# LAB_20200609_0_LightSensorWithNPN.net
KiCad netlist of a schematic drawn in EAGLE
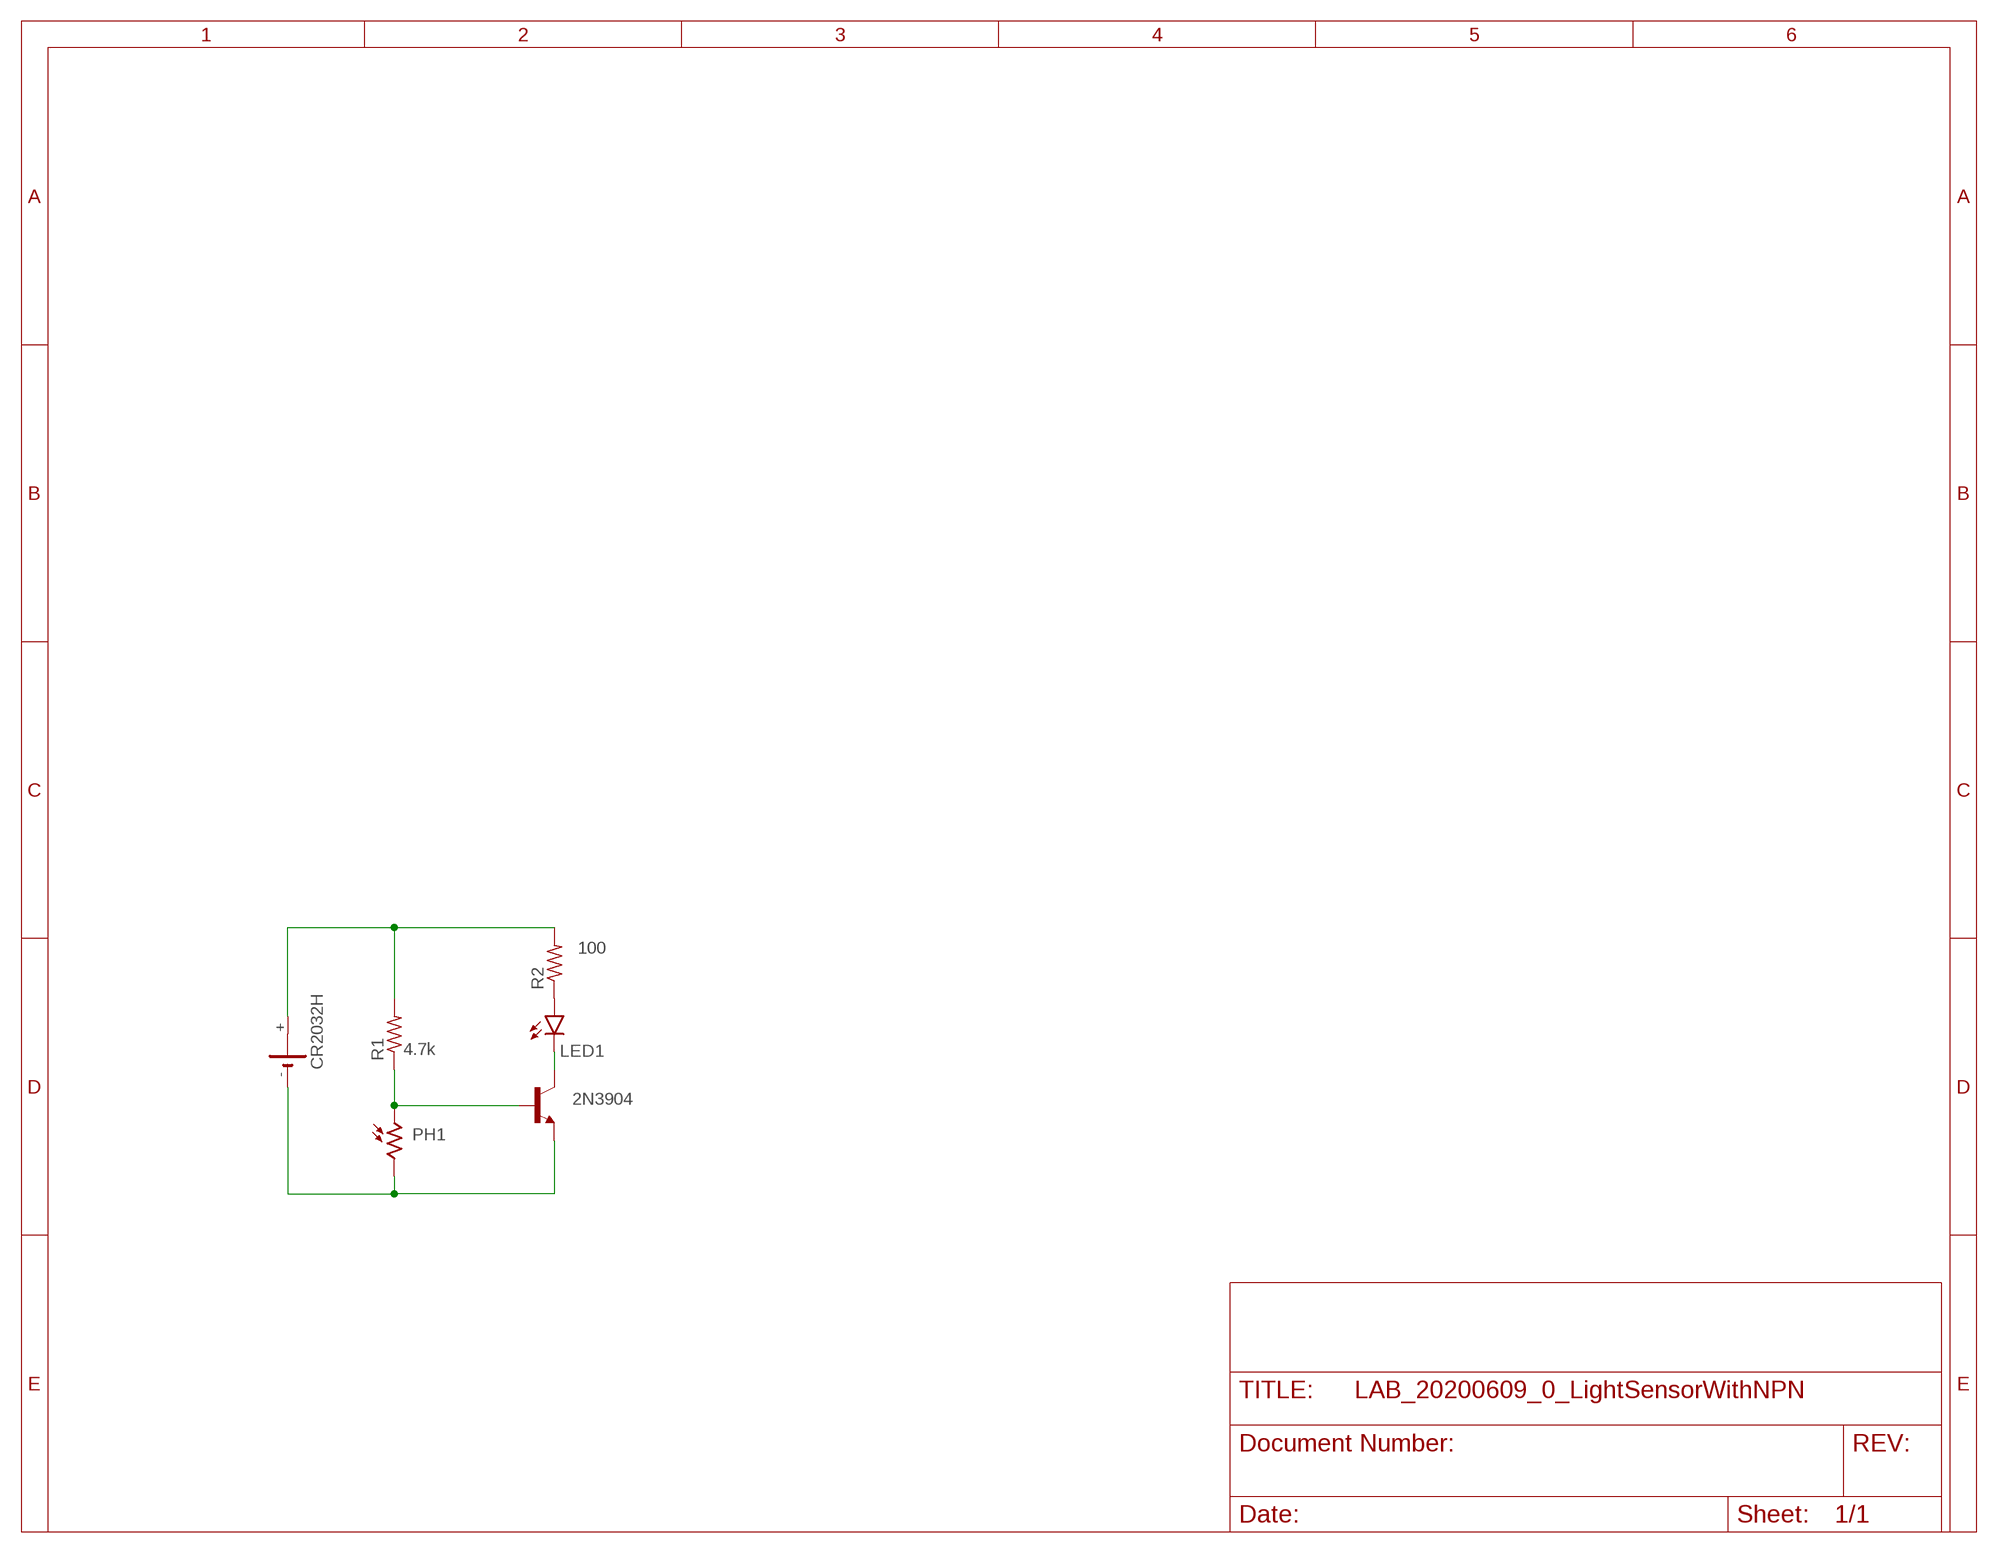
[diagram p0: schematic, sheet 1]

(export (version "E")
  (design (tool "Eeschema 10.0.6"))
  (components
    (comp (ref "G1")
      (value "CR2032H")
      (footprint "eagle-import:CR2032H")
      (libsource (lib "eagle-import") (part "CR2032H"))
    )
    (comp (ref "LED1")
      (value "LAP4-TOP")
      (footprint "eagle-import:P47F-TOP")
      (libsource (lib "eagle-import") (part "P4-TOPLA"))
    )
    (comp (ref "PH1")
      (value "D1160_12")
      (footprint "eagle-import:D11XX")
      (libsource (lib "eagle-import") (part "D1160_12"))
    )
    (comp (ref "R1")
      (value "4.7k")
      (footprint "eagle-import:0207_12")
      (libsource (lib "eagle-import") (part "R-US_0207/12"))
    )
    (comp (ref "R2")
      (value "100")
      (footprint "eagle-import:0207_12")
      (libsource (lib "eagle-import") (part "R-US_0207/12"))
    )
    (comp (ref "T1")
      (value "2N3904")
      (footprint "eagle-import:TO92")
      (libsource (lib "eagle-import") (part "2N3904"))
    )
  )
  (nets
    (net (code "1") (name "Net-(G1-Pad+)") (class "Default")
      (node (ref "G1") (pin "+") (pinfunction "+_+") (pintype "passive"))
      (node (ref "R1") (pin "2") (pinfunction "2_2") (pintype "passive"))
      (node (ref "R2") (pin "2") (pinfunction "2_2") (pintype "passive"))
    )
    (net (code "2") (name "Net-(LED1-PadA)") (class "Default")
      (node (ref "LED1") (pin "A") (pinfunction "A_A") (pintype "passive"))
      (node (ref "R2") (pin "1") (pinfunction "1_1") (pintype "passive"))
    )
    (net (code "3") (name "Net-(T1-B)") (class "Default")
      (node (ref "PH1") (pin "1") (pinfunction "1_1") (pintype "passive"))
      (node (ref "R1") (pin "1") (pinfunction "1_1") (pintype "passive"))
      (node (ref "T1") (pin "2") (pinfunction "B_2") (pintype "passive"))
    )
    (net (code "4") (name "Net-(T1-C)") (class "Default")
      (node (ref "LED1") (pin "C") (pinfunction "C_C") (pintype "passive"))
      (node (ref "T1") (pin "1") (pinfunction "C_1") (pintype "passive"))
    )
    (net (code "5") (name "Net-(T1-E)") (class "Default")
      (node (ref "G1") (pin "-") (pinfunction "-_-") (pintype "passive"))
      (node (ref "PH1") (pin "2") (pinfunction "2_2") (pintype "passive"))
      (node (ref "T1") (pin "3") (pinfunction "E_3") (pintype "passive"))
    )
    (net (code "6") (name "unconnected-(G1-+-Pad+@1)") (class "Default")
      (node (ref "G1") (pin "+@1") (pinfunction "+_+@1") (pintype "passive"))
    )
  )
)
